# CTD_bluetooth_revA.net
KiCad netlist of a schematic drawn in EAGLE
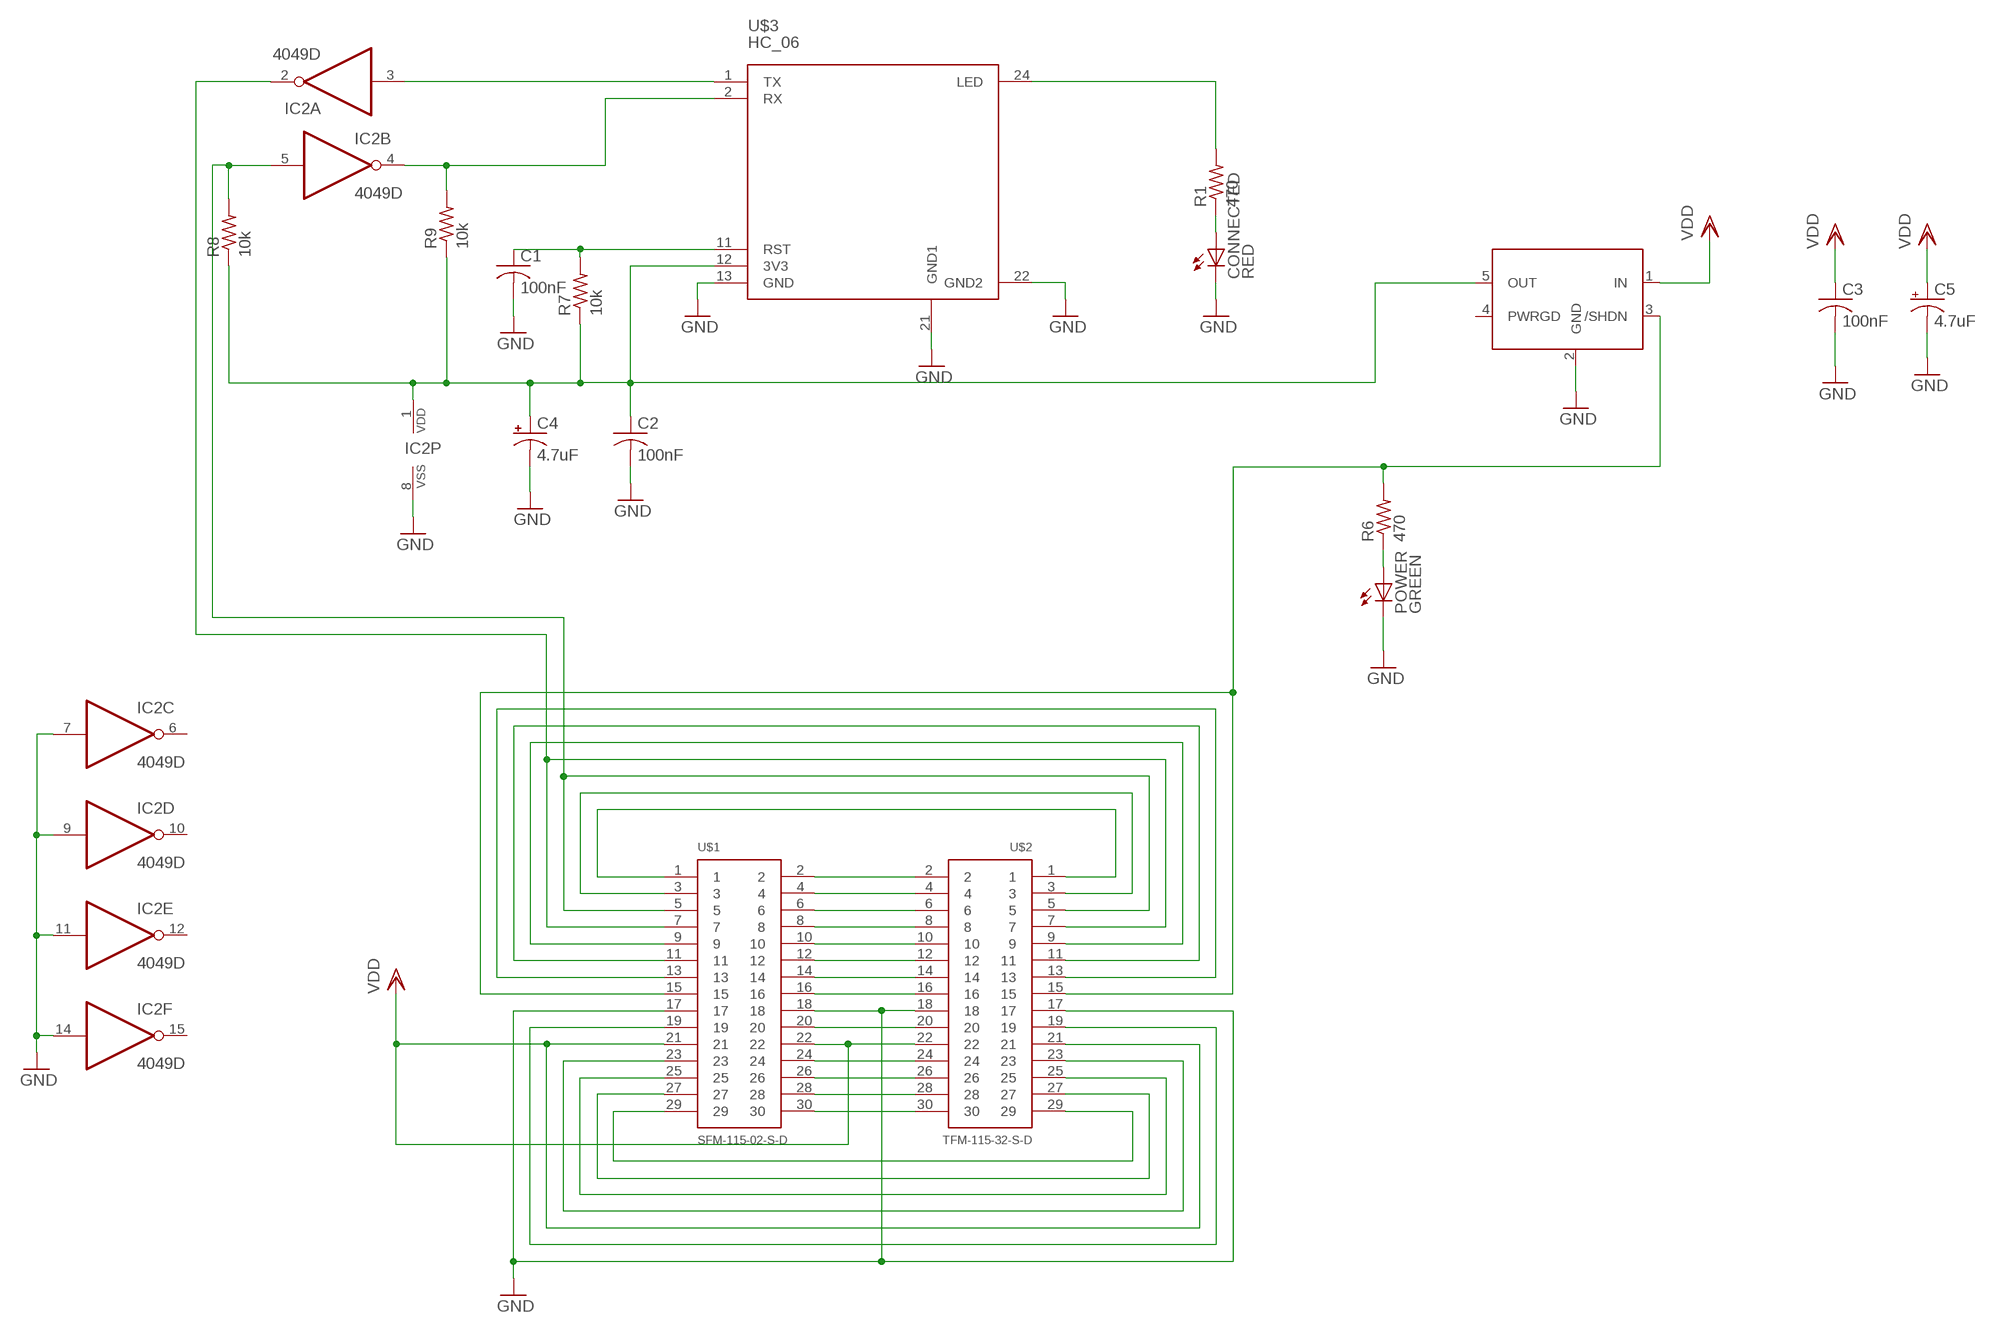
[diagram p0: schematic, sheet 1]

(export (version "E")
  (design (tool "Eeschema 10.0.6"))
  (components
    (comp (ref "C1")
      (value "100nF")
      (footprint "eagle-import:C050-024X044")
      (libsource (lib "eagle-import") (part "C-US050-024X044"))
    )
    (comp (ref "C2")
      (value "100nF")
      (footprint "eagle-import:C050-024X044")
      (libsource (lib "eagle-import") (part "C-US050-024X044"))
    )
    (comp (ref "C3")
      (value "100nF")
      (footprint "eagle-import:C050-024X044")
      (libsource (lib "eagle-import") (part "C-US050-024X044"))
    )
    (comp (ref "C4")
      (value "4.7uF")
      (footprint "eagle-import:153CLV-0505")
      (libsource (lib "eagle-import") (part "CPOL-US153CLV-0505"))
    )
    (comp (ref "C5")
      (value "4.7uF")
      (footprint "eagle-import:153CLV-0505")
      (libsource (lib "eagle-import") (part "CPOL-US153CLV-0505"))
    )
    (comp (ref "CONNECTED")
      (value "RED")
      (footprint "eagle-import:1206")
      (libsource (lib "eagle-import") (part "LEDSMT1206"))
    )
    (comp (ref "IC2")
      (value "4049D")
      (footprint "eagle-import:SO16")
      (libsource (lib "eagle-import") (part "4049D"))
    )
    (comp (ref "POWER")
      (value "GREEN")
      (footprint "eagle-import:1206")
      (libsource (lib "eagle-import") (part "LEDSMT1206"))
    )
    (comp (ref "R1")
      (value "470")
      (footprint "eagle-import:R5025")
      (libsource (lib "eagle-import") (part "R-US_R5025"))
    )
    (comp (ref "R6")
      (value "470")
      (footprint "eagle-import:R5025")
      (libsource (lib "eagle-import") (part "R-US_R5025"))
    )
    (comp (ref "R7")
      (value "10k")
      (footprint "eagle-import:R5025")
      (libsource (lib "eagle-import") (part "R-US_R5025"))
    )
    (comp (ref "R8")
      (value "10k")
      (footprint "eagle-import:R5025")
      (libsource (lib "eagle-import") (part "R-US_R5025"))
    )
    (comp (ref "R9")
      (value "10k")
      (footprint "eagle-import:R5025")
      (libsource (lib "eagle-import") (part "R-US_R5025"))
    )
    (comp (ref "U$1")
      (value "SFM-115-02-S-D")
      (footprint "eagle-import:SFM-115-02-S-D")
      (libsource (lib "eagle-import") (part "SFM-115-02-S-D"))
    )
    (comp (ref "U$2")
      (value "TFM-115-32-S-D")
      (footprint "eagle-import:TFM-115-32-S-D")
      (libsource (lib "eagle-import") (part "TFM-115-32-S-D"))
    )
    (comp (ref "U$3")
      (value "HC_06")
      (footprint "eagle-import:BLUETOOTH_SMD_HC06")
      (libsource (lib "eagle-import") (part "HC_06"))
    )
    (comp (ref "U$4")
      (value "MCP1755T")
      (footprint "eagle-import:SOT23-5")
      (libsource (lib "eagle-import") (part "MCP1755T"))
    )
  )
  (nets
    (net (code "1") (name "GND") (class "Default")
      (node (ref "C1") (pin "2") (pinfunction "2_2") (pintype "passive"))
      (node (ref "C2") (pin "2") (pinfunction "2_2") (pintype "passive"))
      (node (ref "C3") (pin "2") (pinfunction "2_2") (pintype "passive"))
      (node (ref "C4") (pin "-") (pinfunction "-_-") (pintype "passive"))
      (node (ref "C5") (pin "-") (pinfunction "-_-") (pintype "passive"))
      (node (ref "CONNECTED") (pin "C") (pinfunction "C_C") (pintype "passive"))
      (node (ref "IC2") (pin "11") (pinfunction "I_11") (pintype "input"))
      (node (ref "IC2") (pin "14") (pinfunction "I_14") (pintype "input"))
      (node (ref "IC2") (pin "7") (pinfunction "I_7") (pintype "input"))
      (node (ref "IC2") (pin "8") (pinfunction "VSS_8") (pintype "power_in"))
      (node (ref "IC2") (pin "9") (pinfunction "I_9") (pintype "input"))
      (node (ref "POWER") (pin "C") (pinfunction "C_C") (pintype "passive"))
      (node (ref "U$1") (pin "17") (pinfunction "17_17") (pintype "bidirectional"))
      (node (ref "U$1") (pin "18") (pinfunction "18_18") (pintype "bidirectional"))
      (node (ref "U$2") (pin "17") (pinfunction "17_17") (pintype "bidirectional"))
      (node (ref "U$2") (pin "18") (pinfunction "18_18") (pintype "bidirectional"))
      (node (ref "U$3") (pin "13") (pinfunction "GND_13") (pintype "bidirectional"))
      (node (ref "U$3") (pin "21") (pinfunction "GND1_21") (pintype "bidirectional"))
      (node (ref "U$3") (pin "22") (pinfunction "GND2_22") (pintype "bidirectional"))
      (node (ref "U$4") (pin "2") (pinfunction "GND_2") (pintype "power_in"))
    )
    (net (code "2") (name "Net-(CONNECTED-PadA)") (class "Default")
      (node (ref "CONNECTED") (pin "A") (pinfunction "A_A") (pintype "passive"))
      (node (ref "R1") (pin "1") (pinfunction "1_1") (pintype "passive"))
    )
    (net (code "3") (name "Net-(IC2A-I)") (class "Default")
      (node (ref "IC2") (pin "3") (pinfunction "I_3") (pintype "input"))
      (node (ref "U$3") (pin "1") (pinfunction "TX_1") (pintype "bidirectional"))
    )
    (net (code "4") (name "Net-(IC2A-O)") (class "Default")
      (node (ref "IC2") (pin "2") (pinfunction "O_2") (pintype "output"))
      (node (ref "U$1") (pin "7") (pinfunction "7_7") (pintype "bidirectional"))
      (node (ref "U$2") (pin "7") (pinfunction "7_7") (pintype "bidirectional"))
    )
    (net (code "5") (name "Net-(IC2B-I)") (class "Default")
      (node (ref "IC2") (pin "5") (pinfunction "I_5") (pintype "input"))
      (node (ref "R8") (pin "2") (pinfunction "2_2") (pintype "passive"))
      (node (ref "U$1") (pin "5") (pinfunction "5_5") (pintype "bidirectional"))
      (node (ref "U$2") (pin "5") (pinfunction "5_5") (pintype "bidirectional"))
    )
    (net (code "6") (name "Net-(IC2B-O)") (class "Default")
      (node (ref "IC2") (pin "4") (pinfunction "O_4") (pintype "output"))
      (node (ref "R9") (pin "2") (pinfunction "2_2") (pintype "passive"))
      (node (ref "U$3") (pin "2") (pinfunction "RX_2") (pintype "bidirectional"))
    )
    (net (code "7") (name "Net-(IC2G-VDD)") (class "Default")
      (node (ref "C2") (pin "1") (pinfunction "1_1") (pintype "passive"))
      (node (ref "C4") (pin "+") (pinfunction "+_+") (pintype "passive"))
      (node (ref "IC2") (pin "1") (pinfunction "VDD_1") (pintype "power_in"))
      (node (ref "R7") (pin "1") (pinfunction "1_1") (pintype "passive"))
      (node (ref "R8") (pin "1") (pinfunction "1_1") (pintype "passive"))
      (node (ref "R9") (pin "1") (pinfunction "1_1") (pintype "passive"))
      (node (ref "U$3") (pin "12") (pinfunction "3V3_12") (pintype "bidirectional"))
      (node (ref "U$4") (pin "5") (pinfunction "OUT_5") (pintype "power_in"))
    )
    (net (code "8") (name "Net-(POWER-PadA)") (class "Default")
      (node (ref "POWER") (pin "A") (pinfunction "A_A") (pintype "passive"))
      (node (ref "R6") (pin "1") (pinfunction "1_1") (pintype "passive"))
    )
    (net (code "9") (name "Net-(U$1-Pad1)") (class "Default")
      (node (ref "U$1") (pin "1") (pinfunction "1_1") (pintype "bidirectional"))
      (node (ref "U$2") (pin "1") (pinfunction "1_1") (pintype "bidirectional"))
    )
    (net (code "10") (name "Net-(U$1-Pad2)") (class "Default")
      (node (ref "U$1") (pin "2") (pinfunction "2_2") (pintype "bidirectional"))
      (node (ref "U$2") (pin "2") (pinfunction "2_2") (pintype "bidirectional"))
    )
    (net (code "11") (name "Net-(U$1-Pad3)") (class "Default")
      (node (ref "U$1") (pin "3") (pinfunction "3_3") (pintype "bidirectional"))
      (node (ref "U$2") (pin "3") (pinfunction "3_3") (pintype "bidirectional"))
    )
    (net (code "12") (name "Net-(U$1-Pad4)") (class "Default")
      (node (ref "U$1") (pin "4") (pinfunction "4_4") (pintype "bidirectional"))
      (node (ref "U$2") (pin "4") (pinfunction "4_4") (pintype "bidirectional"))
    )
    (net (code "13") (name "Net-(U$1-Pad6)") (class "Default")
      (node (ref "U$1") (pin "6") (pinfunction "6_6") (pintype "bidirectional"))
      (node (ref "U$2") (pin "6") (pinfunction "6_6") (pintype "bidirectional"))
    )
    (net (code "14") (name "Net-(U$1-Pad8)") (class "Default")
      (node (ref "U$1") (pin "8") (pinfunction "8_8") (pintype "bidirectional"))
      (node (ref "U$2") (pin "8") (pinfunction "8_8") (pintype "bidirectional"))
    )
    (net (code "15") (name "Net-(U$1-Pad9)") (class "Default")
      (node (ref "U$1") (pin "9") (pinfunction "9_9") (pintype "bidirectional"))
      (node (ref "U$2") (pin "9") (pinfunction "9_9") (pintype "bidirectional"))
    )
    (net (code "16") (name "Net-(U$1-Pad10)") (class "Default")
      (node (ref "U$1") (pin "10") (pinfunction "10_10") (pintype "bidirectional"))
      (node (ref "U$2") (pin "10") (pinfunction "10_10") (pintype "bidirectional"))
    )
    (net (code "17") (name "Net-(U$1-Pad11)") (class "Default")
      (node (ref "U$1") (pin "11") (pinfunction "11_11") (pintype "bidirectional"))
      (node (ref "U$2") (pin "11") (pinfunction "11_11") (pintype "bidirectional"))
    )
    (net (code "18") (name "Net-(U$1-Pad12)") (class "Default")
      (node (ref "U$1") (pin "12") (pinfunction "12_12") (pintype "bidirectional"))
      (node (ref "U$2") (pin "12") (pinfunction "12_12") (pintype "bidirectional"))
    )
    (net (code "19") (name "Net-(U$1-Pad13)") (class "Default")
      (node (ref "U$1") (pin "13") (pinfunction "13_13") (pintype "bidirectional"))
      (node (ref "U$2") (pin "13") (pinfunction "13_13") (pintype "bidirectional"))
    )
    (net (code "20") (name "Net-(U$1-Pad14)") (class "Default")
      (node (ref "U$1") (pin "14") (pinfunction "14_14") (pintype "bidirectional"))
      (node (ref "U$2") (pin "14") (pinfunction "14_14") (pintype "bidirectional"))
    )
    (net (code "21") (name "Net-(U$1-Pad16)") (class "Default")
      (node (ref "U$1") (pin "16") (pinfunction "16_16") (pintype "bidirectional"))
      (node (ref "U$2") (pin "16") (pinfunction "16_16") (pintype "bidirectional"))
    )
    (net (code "22") (name "Net-(U$1-Pad19)") (class "Default")
      (node (ref "U$1") (pin "19") (pinfunction "19_19") (pintype "bidirectional"))
      (node (ref "U$2") (pin "19") (pinfunction "19_19") (pintype "bidirectional"))
    )
    (net (code "23") (name "Net-(U$1-Pad20)") (class "Default")
      (node (ref "U$1") (pin "20") (pinfunction "20_20") (pintype "bidirectional"))
      (node (ref "U$2") (pin "20") (pinfunction "20_20") (pintype "bidirectional"))
    )
    (net (code "24") (name "Net-(U$1-Pad23)") (class "Default")
      (node (ref "U$1") (pin "23") (pinfunction "23_23") (pintype "bidirectional"))
      (node (ref "U$2") (pin "23") (pinfunction "23_23") (pintype "bidirectional"))
    )
    (net (code "25") (name "Net-(U$1-Pad24)") (class "Default")
      (node (ref "U$1") (pin "24") (pinfunction "24_24") (pintype "bidirectional"))
      (node (ref "U$2") (pin "24") (pinfunction "24_24") (pintype "bidirectional"))
    )
    (net (code "26") (name "Net-(U$1-Pad25)") (class "Default")
      (node (ref "U$1") (pin "25") (pinfunction "25_25") (pintype "bidirectional"))
      (node (ref "U$2") (pin "25") (pinfunction "25_25") (pintype "bidirectional"))
    )
    (net (code "27") (name "Net-(U$1-Pad26)") (class "Default")
      (node (ref "U$1") (pin "26") (pinfunction "26_26") (pintype "bidirectional"))
      (node (ref "U$2") (pin "26") (pinfunction "26_26") (pintype "bidirectional"))
    )
    (net (code "28") (name "Net-(U$1-Pad27)") (class "Default")
      (node (ref "U$1") (pin "27") (pinfunction "27_27") (pintype "bidirectional"))
      (node (ref "U$2") (pin "27") (pinfunction "27_27") (pintype "bidirectional"))
    )
    (net (code "29") (name "Net-(U$1-Pad28)") (class "Default")
      (node (ref "U$1") (pin "28") (pinfunction "28_28") (pintype "bidirectional"))
      (node (ref "U$2") (pin "28") (pinfunction "28_28") (pintype "bidirectional"))
    )
    (net (code "30") (name "Net-(U$1-Pad29)") (class "Default")
      (node (ref "U$1") (pin "29") (pinfunction "29_29") (pintype "bidirectional"))
      (node (ref "U$2") (pin "29") (pinfunction "29_29") (pintype "bidirectional"))
    )
    (net (code "31") (name "Net-(U$1-Pad30)") (class "Default")
      (node (ref "U$1") (pin "30") (pinfunction "30_30") (pintype "bidirectional"))
      (node (ref "U$2") (pin "30") (pinfunction "30_30") (pintype "bidirectional"))
    )
    (net (code "32") (name "Net-(U$3-LED)") (class "Default")
      (node (ref "R1") (pin "2") (pinfunction "2_2") (pintype "passive"))
      (node (ref "U$3") (pin "24") (pinfunction "LED_24") (pintype "bidirectional"))
    )
    (net (code "33") (name "Net-(U$3-RST)") (class "Default")
      (node (ref "C1") (pin "1") (pinfunction "1_1") (pintype "passive"))
      (node (ref "R7") (pin "2") (pinfunction "2_2") (pintype "passive"))
      (node (ref "U$3") (pin "11") (pinfunction "RST_11") (pintype "bidirectional"))
    )
    (net (code "34") (name "Net-(U$4-{slash}SHDN)") (class "Default")
      (node (ref "R6") (pin "2") (pinfunction "2_2") (pintype "passive"))
      (node (ref "U$1") (pin "15") (pinfunction "15_15") (pintype "bidirectional"))
      (node (ref "U$2") (pin "15") (pinfunction "15_15") (pintype "bidirectional"))
      (node (ref "U$4") (pin "3") (pinfunction "/SHDN_3") (pintype "input"))
    )
    (net (code "35") (name "VDD") (class "Default")
      (node (ref "C3") (pin "1") (pinfunction "1_1") (pintype "passive"))
      (node (ref "C5") (pin "+") (pinfunction "+_+") (pintype "passive"))
      (node (ref "U$1") (pin "21") (pinfunction "21_21") (pintype "bidirectional"))
      (node (ref "U$1") (pin "22") (pinfunction "22_22") (pintype "bidirectional"))
      (node (ref "U$2") (pin "21") (pinfunction "21_21") (pintype "bidirectional"))
      (node (ref "U$2") (pin "22") (pinfunction "22_22") (pintype "bidirectional"))
      (node (ref "U$4") (pin "1") (pinfunction "IN_1") (pintype "power_in"))
    )
    (net (code "36") (name "unconnected-(IC2C-O-Pad6)") (class "Default")
      (node (ref "IC2") (pin "6") (pinfunction "O_6") (pintype "output"))
    )
    (net (code "37") (name "unconnected-(IC2D-O-Pad10)") (class "Default")
      (node (ref "IC2") (pin "10") (pinfunction "O_10") (pintype "output"))
    )
    (net (code "38") (name "unconnected-(IC2E-O-Pad12)") (class "Default")
      (node (ref "IC2") (pin "12") (pinfunction "O_12") (pintype "output"))
    )
    (net (code "39") (name "unconnected-(IC2F-O-Pad15)") (class "Default")
      (node (ref "IC2") (pin "15") (pinfunction "O_15") (pintype "output"))
    )
    (net (code "40") (name "unconnected-(U$4-PWRGD-Pad4)") (class "Default")
      (node (ref "U$4") (pin "4") (pinfunction "PWRGD_4") (pintype "no_connect"))
    )
  )
)
